# LAUNCHXL-F28379D_2.net
KiCad netlist of a schematic drawn in Altium Designer
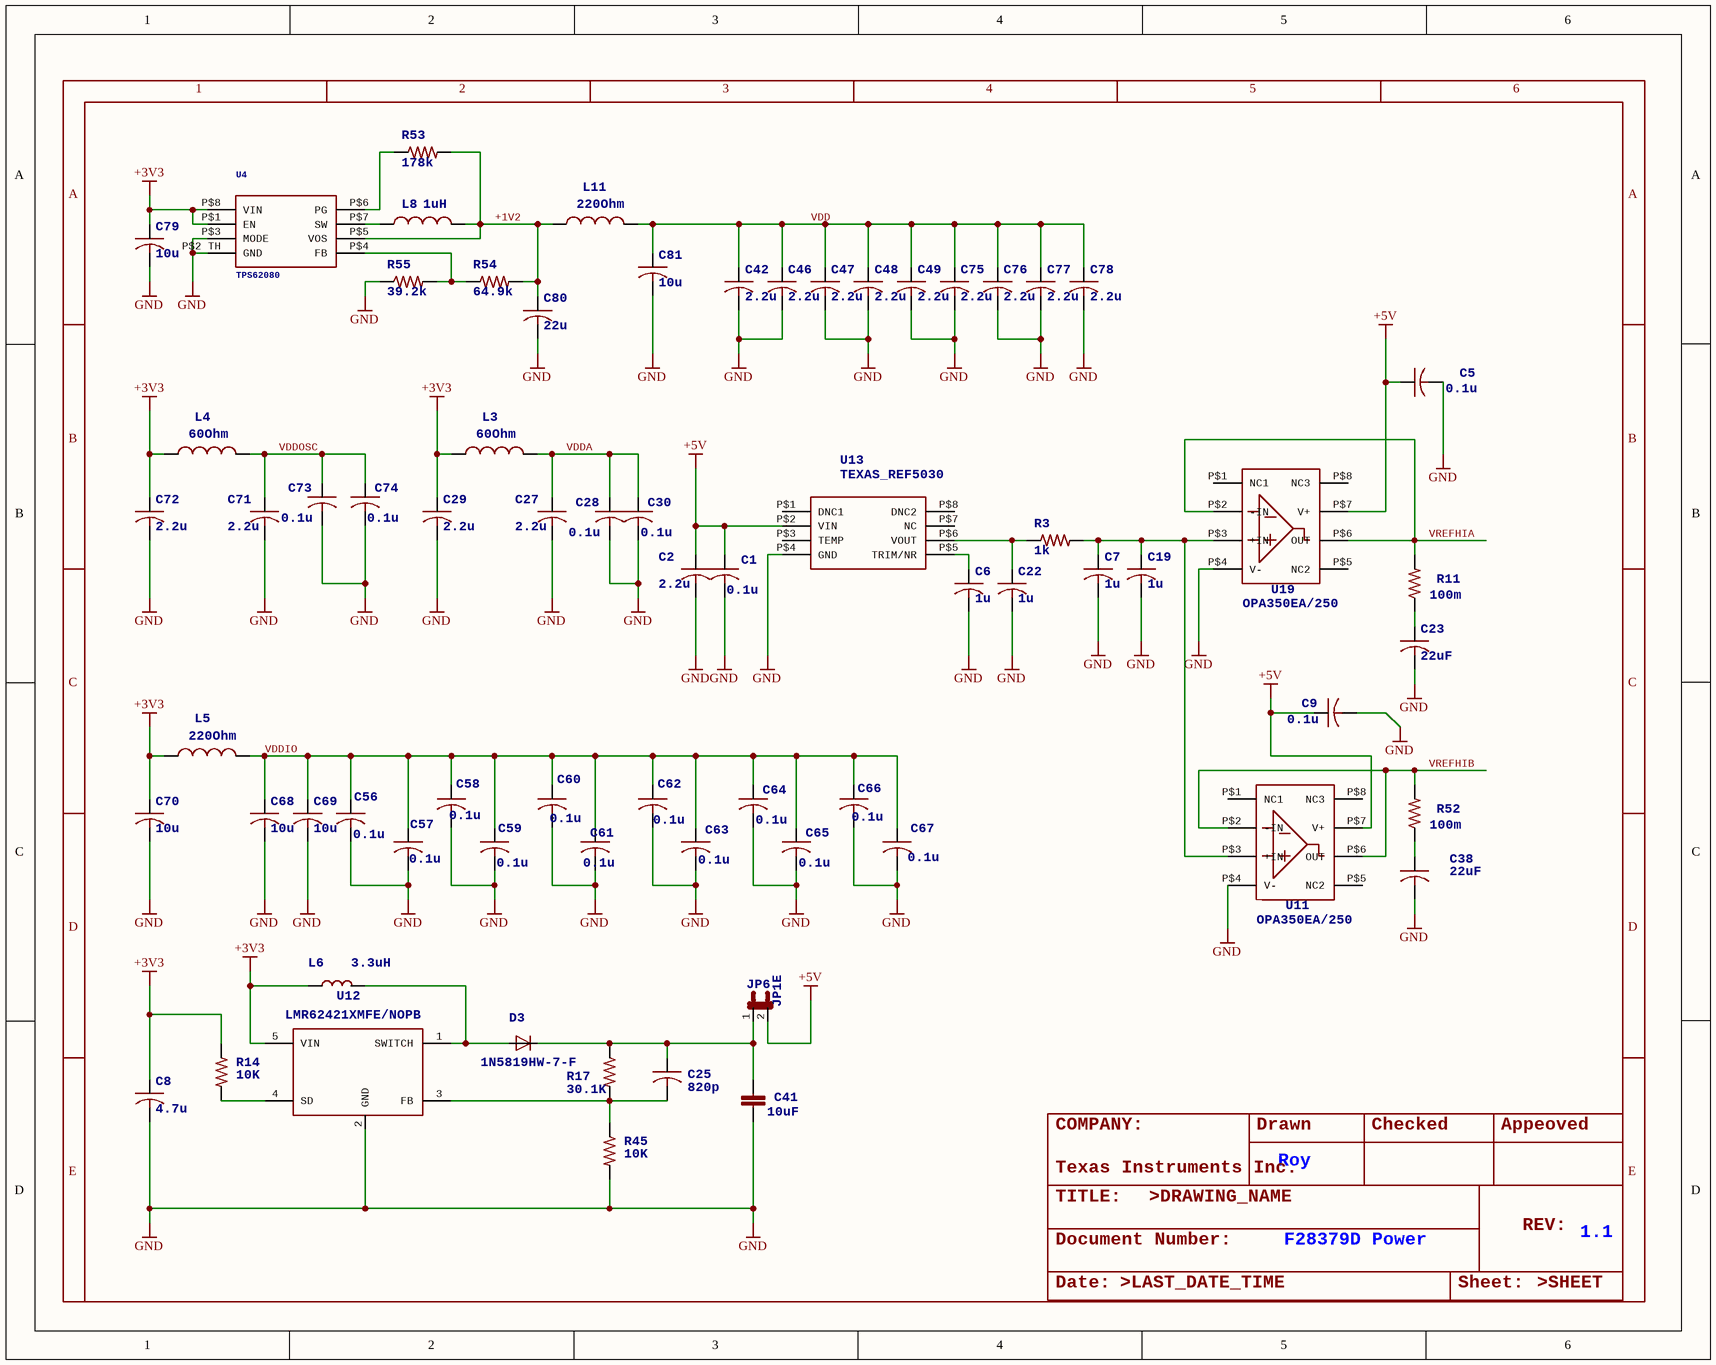
[diagram p0: LAUNCHXL-F28379D_2.SchDoc]

(export (version "E")
  (design (tool "Eeschema 10.0.6"))
  (components
    (comp (ref "C1")
      (value "0.1u")
      (footprint "C0402")
      (description "<B>CAPACITOR</B>, American symbol")
      (libsource (lib "rcl") (part "C-USC0402"))
    )
    (comp (ref "C2")
      (value "2.2u")
      (footprint "C0402")
      (description "<B>CAPACITOR</B>, American symbol")
      (libsource (lib "rcl") (part "C-USC0402"))
    )
    (comp (ref "C5")
      (value "0.1u")
      (footprint "C0402")
      (description "<B>CAPACITOR</B>, American symbol")
      (libsource (lib "rcl") (part "C-USC0402"))
    )
    (comp (ref "C6")
      (value "1u")
      (footprint "C0402")
      (description "<B>CAPACITOR</B>, American symbol")
      (libsource (lib "rcl") (part "C-USC0402"))
    )
    (comp (ref "C7")
      (value "1u")
      (footprint "C0402")
      (description "<B>CAPACITOR</B>, American symbol")
      (libsource (lib "rcl") (part "C-USC0402"))
    )
    (comp (ref "C8")
      (value "4.7u")
      (footprint "C0402")
      (description "<B>CAPACITOR</B>, American symbol")
      (libsource (lib "rcl") (part "C-USC0402"))
    )
    (comp (ref "C9")
      (value "0.1u")
      (footprint "C0402")
      (description "<B>CAPACITOR</B>, American symbol")
      (libsource (lib "rcl") (part "C-USC0402"))
    )
    (comp (ref "C19")
      (value "1u")
      (footprint "C0402")
      (description "<B>CAPACITOR</B>, American symbol")
      (libsource (lib "rcl") (part "C-USC0402"))
    )
    (comp (ref "C22")
      (value "1u")
      (footprint "C0402")
      (description "<B>CAPACITOR</B>, American symbol")
      (libsource (lib "rcl") (part "C-USC0402"))
    )
    (comp (ref "C23")
      (value "22uF")
      (footprint "C0603")
      (description "<B>CAPACITOR</B>, American symbol")
      (libsource (lib "rcl") (part "C-USC0603"))
    )
    (comp (ref "C25")
      (value "820p")
      (footprint "C0402")
      (description "<B>CAPACITOR</B>, American symbol")
      (libsource (lib "rcl") (part "C-USC0402"))
    )
    (comp (ref "C27")
      (value "2.2u")
      (footprint "C0402")
      (description "<B>CAPACITOR</B>, American symbol")
      (libsource (lib "rcl") (part "C-USC0402"))
    )
    (comp (ref "C28")
      (value "0.1u")
      (footprint "C0402")
      (description "<B>CAPACITOR</B>, American symbol")
      (libsource (lib "rcl") (part "C-USC0402"))
    )
    (comp (ref "C29")
      (value "2.2u")
      (footprint "C0402")
      (description "<B>CAPACITOR</B>, American symbol")
      (libsource (lib "rcl") (part "C-USC0402"))
    )
    (comp (ref "C30")
      (value "0.1u")
      (footprint "C0402")
      (description "<B>CAPACITOR</B>, American symbol")
      (libsource (lib "rcl") (part "C-USC0402"))
    )
    (comp (ref "C38")
      (value "22uF")
      (footprint "C0603")
      (description "<B>CAPACITOR</B>, American symbol")
      (libsource (lib "rcl") (part "C-USC0603"))
    )
    (comp (ref "C41")
      (value "10uF")
      (footprint "SPARKFUN_1210")
      (description "<b>Capacitor</b>\nStandard 0603 ceramic capacitor, and 0.1\" leaded capacitor.")
      (libsource (lib "RF430FRL152H_EVM_a") (part "SPARKFUN_CAP1210"))
    )
    (comp (ref "C42")
      (value "2.2u")
      (footprint "C0402")
      (description "<B>CAPACITOR</B>, American symbol")
      (libsource (lib "rcl") (part "C-USC0402"))
    )
    (comp (ref "C46")
      (value "2.2u")
      (footprint "C0402")
      (description "<B>CAPACITOR</B>, American symbol")
      (libsource (lib "rcl") (part "C-USC0402"))
    )
    (comp (ref "C47")
      (value "2.2u")
      (footprint "C0402")
      (description "<B>CAPACITOR</B>, American symbol")
      (libsource (lib "rcl") (part "C-USC0402"))
    )
    (comp (ref "C48")
      (value "2.2u")
      (footprint "C0402")
      (description "<B>CAPACITOR</B>, American symbol")
      (libsource (lib "rcl") (part "C-USC0402"))
    )
    (comp (ref "C49")
      (value "2.2u")
      (footprint "C0402")
      (description "<B>CAPACITOR</B>, American symbol")
      (libsource (lib "rcl") (part "C-USC0402"))
    )
    (comp (ref "C56")
      (value "0.1u")
      (footprint "C0402")
      (description "<B>CAPACITOR</B>, American symbol")
      (libsource (lib "rcl") (part "C-USC0402"))
    )
    (comp (ref "C57")
      (value "0.1u")
      (footprint "C0402")
      (description "<B>CAPACITOR</B>, American symbol")
      (libsource (lib "") (part "C-USC0402_1"))
    )
    (comp (ref "C58")
      (value "0.1u")
      (footprint "C0402")
      (description "<B>CAPACITOR</B>, American symbol")
      (libsource (lib "rcl") (part "C-USC0402"))
    )
    (comp (ref "C59")
      (value "0.1u")
      (footprint "C0402")
      (description "<B>CAPACITOR</B>, American symbol")
      (libsource (lib "rcl") (part "C-USC0402"))
    )
    (comp (ref "C60")
      (value "0.1u")
      (footprint "C0402")
      (description "<B>CAPACITOR</B>, American symbol")
      (libsource (lib "rcl") (part "C-USC0402"))
    )
    (comp (ref "C61")
      (value "0.1u")
      (footprint "C0402")
      (description "<B>CAPACITOR</B>, American symbol")
      (libsource (lib "rcl") (part "C-USC0402"))
    )
    (comp (ref "C62")
      (value "0.1u")
      (footprint "C0402")
      (description "<B>CAPACITOR</B>, American symbol")
      (libsource (lib "rcl") (part "C-USC0402"))
    )
    (comp (ref "C63")
      (value "0.1u")
      (footprint "C0402")
      (description "<B>CAPACITOR</B>, American symbol")
      (libsource (lib "rcl") (part "C-USC0402"))
    )
    (comp (ref "C64")
      (value "0.1u")
      (footprint "C0402")
      (description "<B>CAPACITOR</B>, American symbol")
      (libsource (lib "rcl") (part "C-USC0402"))
    )
    (comp (ref "C65")
      (value "0.1u")
      (footprint "C0402")
      (description "<B>CAPACITOR</B>, American symbol")
      (libsource (lib "rcl") (part "C-USC0402"))
    )
    (comp (ref "C66")
      (value "0.1u")
      (footprint "C0402")
      (description "<B>CAPACITOR</B>, American symbol")
      (libsource (lib "rcl") (part "C-USC0402"))
    )
    (comp (ref "C67")
      (value "0.1u")
      (footprint "C0402")
      (description "<B>CAPACITOR</B>, American symbol")
      (libsource (lib "rcl") (part "C-USC0402"))
    )
    (comp (ref "C68")
      (value "10u")
      (footprint "C0603")
      (description "<B>CAPACITOR</B>, American symbol")
      (libsource (lib "rcl") (part "C-USC0603"))
    )
    (comp (ref "C69")
      (value "10u")
      (footprint "C0603")
      (description "<B>CAPACITOR</B>, American symbol")
      (libsource (lib "rcl") (part "C-USC0603"))
    )
    (comp (ref "C70")
      (value "10u")
      (footprint "C0603")
      (description "<B>CAPACITOR</B>, American symbol")
      (libsource (lib "rcl") (part "C-USC0603"))
    )
    (comp (ref "C71")
      (value "2.2u")
      (footprint "C0402")
      (description "<B>CAPACITOR</B>, American symbol")
      (libsource (lib "rcl") (part "C-USC0402"))
    )
    (comp (ref "C72")
      (value "2.2u")
      (footprint "C0402")
      (description "<B>CAPACITOR</B>, American symbol")
      (libsource (lib "rcl") (part "C-USC0402"))
    )
    (comp (ref "C73")
      (value "0.1u")
      (footprint "C0402")
      (description "<B>CAPACITOR</B>, American symbol")
      (libsource (lib "rcl") (part "C-USC0402"))
    )
    (comp (ref "C74")
      (value "0.1u")
      (footprint "C0402")
      (description "<B>CAPACITOR</B>, American symbol")
      (libsource (lib "rcl") (part "C-USC0402"))
    )
    (comp (ref "C75")
      (value "2.2u")
      (footprint "C0402")
      (description "<B>CAPACITOR</B>, American symbol")
      (libsource (lib "rcl") (part "C-USC0402"))
    )
    (comp (ref "C76")
      (value "2.2u")
      (footprint "C0402")
      (description "<B>CAPACITOR</B>, American symbol")
      (libsource (lib "rcl") (part "C-USC0402"))
    )
    (comp (ref "C77")
      (value "2.2u")
      (footprint "C0402")
      (description "<B>CAPACITOR</B>, American symbol")
      (libsource (lib "rcl") (part "C-USC0402"))
    )
    (comp (ref "C78")
      (value "2.2u")
      (footprint "C0402")
      (description "<B>CAPACITOR</B>, American symbol")
      (libsource (lib "rcl") (part "C-USC0402"))
    )
    (comp (ref "C79")
      (value "10u")
      (footprint "C0603")
      (description "<B>CAPACITOR</B>, American symbol")
      (libsource (lib "rcl") (part "C-USC0603"))
    )
    (comp (ref "C80")
      (value "22u")
      (footprint "C0603")
      (description "<B>CAPACITOR</B>, American symbol")
      (libsource (lib "rcl") (part "C-USC0603"))
    )
    (comp (ref "C81")
      (value "10u")
      (footprint "C0603")
      (description "<B>CAPACITOR</B>, American symbol")
      (libsource (lib "rcl") (part "C-USC0603"))
    )
    (comp (ref "D3")
      (value "1N5819HW-7-F")
      (footprint "SOD123")
      (description "<B>DIODE</B><p>\nhigh speed (Philips)")
      (libsource (lib "diode") (part "1N4148"))
    )
    (comp (ref "JP6")
      (value "JP1E")
      (footprint "JP1")
      (description "<b>JUMPER</b>")
      (libsource (lib "jumper") (part "JP1E"))
    )
    (comp (ref "L3")
      (value "60Ohm")
      (footprint "R0402")
      (description "<B>INDUCTOR</B>, American symbol")
      (libsource (lib "rcl") (part "L-US0402"))
    )
    (comp (ref "L4")
      (value "60Ohm")
      (footprint "R0402")
      (description "<B>INDUCTOR</B>, American symbol")
      (libsource (lib "rcl") (part "L-US0402"))
    )
    (comp (ref "L5")
      (value "220Ohm")
      (footprint "R0402")
      (description "<B>INDUCTOR</B>, American symbol")
      (libsource (lib "rcl") (part "L-US0402"))
    )
    (comp (ref "L6")
      (value "3.3uH")
      (footprint "INDUCT-3_7*3_5")
      (libsource (lib "LAUNCHXL-F28027") (part "VLF4012A"))
    )
    (comp (ref "L8")
      (value "1uH")
      (footprint "L1212")
      (description "<B>INDUCTOR</B>, American symbol")
      (libsource (lib "LAUNCHXL-F28377S") (part "L-USL1212"))
    )
    (comp (ref "L11")
      (value "220Ohm")
      (footprint "R0402")
      (description "<B>INDUCTOR</B>, American symbol")
      (libsource (lib "rcl") (part "L-US0402"))
    )
    (comp (ref "R3")
      (value "1k")
      (footprint "R0402")
      (description "<B>RESISTOR</B>, American symbol")
      (libsource (lib "rcl") (part "R-US_R0402"))
    )
    (comp (ref "R11")
      (value "100m")
      (footprint "R0402")
      (description "<B>RESISTOR</B>, American symbol")
      (libsource (lib "rcl") (part "R-US_R0402"))
    )
    (comp (ref "R14")
      (value "10K")
      (footprint "R0402")
      (description "<B>RESISTOR</B>, American symbol")
      (libsource (lib "rcl") (part "R-US_R0402"))
    )
    (comp (ref "R17")
      (value "30.1K")
      (footprint "R0402")
      (description "<B>RESISTOR</B>, American symbol")
      (libsource (lib "rcl") (part "R-US_R0402"))
    )
    (comp (ref "R45")
      (value "10K")
      (footprint "R0402")
      (description "<B>RESISTOR</B>, American symbol")
      (libsource (lib "rcl") (part "R-US_R0402"))
    )
    (comp (ref "R52")
      (value "100m")
      (footprint "R0402")
      (description "<B>RESISTOR</B>, American symbol")
      (libsource (lib "rcl") (part "R-US_R0402"))
    )
    (comp (ref "R53")
      (value "178k")
      (footprint "R0402")
      (description "<B>RESISTOR</B>, American symbol")
      (libsource (lib "rcl") (part "R-US_R0402"))
    )
    (comp (ref "R54")
      (value "64.9k")
      (footprint "R0402")
      (description "<B>RESISTOR</B>, American symbol")
      (libsource (lib "rcl") (part "R-US_R0402"))
    )
    (comp (ref "R55")
      (value "39.2k")
      (footprint "R0402")
      (description "<B>RESISTOR</B>, American symbol")
      (libsource (lib "rcl") (part "R-US_R0402"))
    )
    (comp (ref "U4")
      (value "TPS62080")
      (footprint "SON8")
      (libsource (lib "LAUNCHXL-F28377S") (part "TPS62080"))
    )
    (comp (ref "U11")
      (value "OPA350EA/250")
      (footprint "OPA350_OPA350")
      (libsource (lib "OPA350") (part "OPA350_OPA350"))
    )
    (comp (ref "U12")
      (value "LMR62421XMFE/NOPB")
      (footprint "SOT23-5-DBV")
      (libsource (lib "LAUNCHXL-F28027") (part "LMR62421XMFE/NOPB"))
    )
    (comp (ref "U13")
      (value "TEXAS_REF5030")
      (footprint "TEXAS_REF5030")
      (libsource (lib "texas") (part "TEXAS_REF5030"))
    )
    (comp (ref "U19")
      (value "OPA350EA/250")
      (footprint "OPA350_OPA350")
      (libsource (lib "OPA350") (part "OPA350_OPA350"))
    )
  )
  (nets
    (net (code "1") (name "+3V3") (class "Default")
      (node (ref "C29") (pin "1") (pinfunction "1_1") (pintype "passive"))
      (node (ref "C70") (pin "1") (pinfunction "1_1") (pintype "passive"))
      (node (ref "C72") (pin "1") (pinfunction "1_1") (pintype "passive"))
      (node (ref "C79") (pin "1") (pinfunction "1_1") (pintype "passive"))
      (node (ref "C8") (pin "1") (pinfunction "1_1") (pintype "passive"))
      (node (ref "L3") (pin "1") (pinfunction "1_1") (pintype "passive"))
      (node (ref "L4") (pin "1") (pinfunction "1_1") (pintype "passive"))
      (node (ref "L5") (pin "1") (pinfunction "1_1") (pintype "passive"))
      (node (ref "L6") (pin "P$1") (pinfunction "1_P$1") (pintype "passive"))
      (node (ref "R14") (pin "1") (pinfunction "1_1") (pintype "passive"))
      (node (ref "U12") (pin "5") (pinfunction "VIN_5") (pintype "passive"))
      (node (ref "U4") (pin "P$1") (pinfunction "EN_P$1") (pintype "passive"))
      (node (ref "U4") (pin "P$8") (pinfunction "VIN_P$8") (pintype "passive"))
    )
    (net (code "2") (name "+5V") (class "Default")
      (node (ref "C1") (pin "1") (pinfunction "1_1") (pintype "passive"))
      (node (ref "C2") (pin "1") (pinfunction "1_1") (pintype "passive"))
      (node (ref "C5") (pin "1") (pinfunction "1_1") (pintype "passive"))
      (node (ref "C9") (pin "1") (pinfunction "1_1") (pintype "passive"))
      (node (ref "JP6") (pin "2") (pinfunction "2_2") (pintype "passive"))
      (node (ref "U11") (pin "P$7") (pinfunction "V+_P$7") (pintype "passive"))
      (node (ref "U13") (pin "P$2") (pinfunction "VIN_P$2") (pintype "passive"))
      (node (ref "U19") (pin "P$7") (pinfunction "V+_P$7") (pintype "passive"))
    )
    (net (code "3") (name "/+1V2") (class "Default")
      (node (ref "C80") (pin "1") (pinfunction "1_1") (pintype "passive"))
      (node (ref "L11") (pin "1") (pinfunction "1_1") (pintype "passive"))
      (node (ref "L8") (pin "P$2") (pinfunction "2_P$2") (pintype "passive"))
      (node (ref "R53") (pin "2") (pinfunction "2_2") (pintype "passive"))
      (node (ref "R54") (pin "2") (pinfunction "2_2") (pintype "passive"))
      (node (ref "U4") (pin "P$5") (pinfunction "VOS_P$5") (pintype "passive"))
    )
    (net (code "4") (name "/VDD") (class "Default")
      (node (ref "C42") (pin "1") (pinfunction "1_1") (pintype "passive"))
      (node (ref "C46") (pin "1") (pinfunction "1_1") (pintype "passive"))
      (node (ref "C47") (pin "1") (pinfunction "1_1") (pintype "passive"))
      (node (ref "C48") (pin "1") (pinfunction "1_1") (pintype "passive"))
      (node (ref "C49") (pin "1") (pinfunction "1_1") (pintype "passive"))
      (node (ref "C75") (pin "1") (pinfunction "1_1") (pintype "passive"))
      (node (ref "C76") (pin "1") (pinfunction "1_1") (pintype "passive"))
      (node (ref "C77") (pin "1") (pinfunction "1_1") (pintype "passive"))
      (node (ref "C78") (pin "1") (pinfunction "1_1") (pintype "passive"))
      (node (ref "C81") (pin "1") (pinfunction "1_1") (pintype "passive"))
      (node (ref "L11") (pin "2") (pinfunction "2_2") (pintype "passive"))
    )
    (net (code "5") (name "/VDDA") (class "Default")
      (node (ref "C27") (pin "1") (pinfunction "1_1") (pintype "passive"))
      (node (ref "C28") (pin "1") (pinfunction "1_1") (pintype "passive"))
      (node (ref "C30") (pin "1") (pinfunction "1_1") (pintype "passive"))
      (node (ref "L3") (pin "2") (pinfunction "2_2") (pintype "passive"))
    )
    (net (code "6") (name "/VDDIO") (class "Default")
      (node (ref "C56") (pin "1") (pinfunction "1_1") (pintype "passive"))
      (node (ref "C57") (pin "1") (pinfunction "1_1") (pintype "passive"))
      (node (ref "C58") (pin "1") (pinfunction "1_1") (pintype "passive"))
      (node (ref "C59") (pin "1") (pinfunction "1_1") (pintype "passive"))
      (node (ref "C60") (pin "1") (pinfunction "1_1") (pintype "passive"))
      (node (ref "C61") (pin "1") (pinfunction "1_1") (pintype "passive"))
      (node (ref "C62") (pin "1") (pinfunction "1_1") (pintype "passive"))
      (node (ref "C63") (pin "1") (pinfunction "1_1") (pintype "passive"))
      (node (ref "C64") (pin "1") (pinfunction "1_1") (pintype "passive"))
      (node (ref "C65") (pin "1") (pinfunction "1_1") (pintype "passive"))
      (node (ref "C66") (pin "1") (pinfunction "1_1") (pintype "passive"))
      (node (ref "C67") (pin "1") (pinfunction "1_1") (pintype "passive"))
      (node (ref "C68") (pin "1") (pinfunction "1_1") (pintype "passive"))
      (node (ref "C69") (pin "1") (pinfunction "1_1") (pintype "passive"))
      (node (ref "L5") (pin "2") (pinfunction "2_2") (pintype "passive"))
    )
    (net (code "7") (name "/VDDOSC") (class "Default")
      (node (ref "C71") (pin "1") (pinfunction "1_1") (pintype "passive"))
      (node (ref "C73") (pin "1") (pinfunction "1_1") (pintype "passive"))
      (node (ref "C74") (pin "1") (pinfunction "1_1") (pintype "passive"))
      (node (ref "L4") (pin "2") (pinfunction "2_2") (pintype "passive"))
    )
    (net (code "8") (name "/VREFHIA") (class "Default")
      (node (ref "R11") (pin "2") (pinfunction "2_2") (pintype "passive"))
      (node (ref "U19") (pin "P$2") (pinfunction "-IN_P$2") (pintype "passive"))
      (node (ref "U19") (pin "P$6") (pinfunction "OUT_P$6") (pintype "passive"))
    )
    (net (code "9") (name "/VREFHIB") (class "Default")
      (node (ref "R52") (pin "2") (pinfunction "2_2") (pintype "passive"))
      (node (ref "U11") (pin "P$2") (pinfunction "-IN_P$2") (pintype "passive"))
      (node (ref "U11") (pin "P$6") (pinfunction "OUT_P$6") (pintype "passive"))
    )
    (net (code "10") (name "GND") (class "Default")
      (node (ref "C1") (pin "2") (pinfunction "2_2") (pintype "passive"))
      (node (ref "C19") (pin "2") (pinfunction "2_2") (pintype "passive"))
      (node (ref "C2") (pin "2") (pinfunction "2_2") (pintype "passive"))
      (node (ref "C22") (pin "2") (pinfunction "2_2") (pintype "passive"))
      (node (ref "C23") (pin "2") (pinfunction "2_2") (pintype "passive"))
      (node (ref "C27") (pin "2") (pinfunction "2_2") (pintype "passive"))
      (node (ref "C28") (pin "2") (pinfunction "2_2") (pintype "passive"))
      (node (ref "C29") (pin "2") (pinfunction "2_2") (pintype "passive"))
      (node (ref "C30") (pin "2") (pinfunction "2_2") (pintype "passive"))
      (node (ref "C38") (pin "2") (pinfunction "2_2") (pintype "passive"))
      (node (ref "C41") (pin "1") (pinfunction "1_1") (pintype "passive"))
      (node (ref "C42") (pin "2") (pinfunction "2_2") (pintype "passive"))
      (node (ref "C46") (pin "2") (pinfunction "2_2") (pintype "passive"))
      (node (ref "C47") (pin "2") (pinfunction "2_2") (pintype "passive"))
      (node (ref "C48") (pin "2") (pinfunction "2_2") (pintype "passive"))
      (node (ref "C49") (pin "2") (pinfunction "2_2") (pintype "passive"))
      (node (ref "C5") (pin "2") (pinfunction "2_2") (pintype "passive"))
      (node (ref "C56") (pin "2") (pinfunction "2_2") (pintype "passive"))
      (node (ref "C57") (pin "2") (pinfunction "2_2") (pintype "passive"))
      (node (ref "C58") (pin "2") (pinfunction "2_2") (pintype "passive"))
      (node (ref "C59") (pin "2") (pinfunction "2_2") (pintype "passive"))
      (node (ref "C6") (pin "2") (pinfunction "2_2") (pintype "passive"))
      (node (ref "C60") (pin "2") (pinfunction "2_2") (pintype "passive"))
      (node (ref "C61") (pin "2") (pinfunction "2_2") (pintype "passive"))
      (node (ref "C62") (pin "2") (pinfunction "2_2") (pintype "passive"))
      (node (ref "C63") (pin "2") (pinfunction "2_2") (pintype "passive"))
      (node (ref "C64") (pin "2") (pinfunction "2_2") (pintype "passive"))
      (node (ref "C65") (pin "2") (pinfunction "2_2") (pintype "passive"))
      (node (ref "C66") (pin "2") (pinfunction "2_2") (pintype "passive"))
      (node (ref "C67") (pin "2") (pinfunction "2_2") (pintype "passive"))
      (node (ref "C68") (pin "2") (pinfunction "2_2") (pintype "passive"))
      (node (ref "C69") (pin "2") (pinfunction "2_2") (pintype "passive"))
      (node (ref "C7") (pin "2") (pinfunction "2_2") (pintype "passive"))
      (node (ref "C70") (pin "2") (pinfunction "2_2") (pintype "passive"))
      (node (ref "C71") (pin "2") (pinfunction "2_2") (pintype "passive"))
      (node (ref "C72") (pin "2") (pinfunction "2_2") (pintype "passive"))
      (node (ref "C73") (pin "2") (pinfunction "2_2") (pintype "passive"))
      (node (ref "C74") (pin "2") (pinfunction "2_2") (pintype "passive"))
      (node (ref "C75") (pin "2") (pinfunction "2_2") (pintype "passive"))
      (node (ref "C76") (pin "2") (pinfunction "2_2") (pintype "passive"))
      (node (ref "C77") (pin "2") (pinfunction "2_2") (pintype "passive"))
      (node (ref "C78") (pin "2") (pinfunction "2_2") (pintype "passive"))
      (node (ref "C79") (pin "2") (pinfunction "2_2") (pintype "passive"))
      (node (ref "C8") (pin "2") (pinfunction "2_2") (pintype "passive"))
      (node (ref "C80") (pin "2") (pinfunction "2_2") (pintype "passive"))
      (node (ref "C81") (pin "2") (pinfunction "2_2") (pintype "passive"))
      (node (ref "C9") (pin "2") (pinfunction "2_2") (pintype "passive"))
      (node (ref "R45") (pin "2") (pinfunction "2_2") (pintype "passive"))
      (node (ref "R55") (pin "1") (pinfunction "1_1") (pintype "passive"))
      (node (ref "U11") (pin "P$4") (pinfunction "V-_P$4") (pintype "passive"))
      (node (ref "U12") (pin "2") (pinfunction "GND_2") (pintype "passive"))
      (node (ref "U13") (pin "P$4") (pinfunction "GND_P$4") (pintype "passive"))
      (node (ref "U19") (pin "P$4") (pinfunction "V-_P$4") (pintype "passive"))
      (node (ref "U4") (pin "P$2_TH") (pinfunction "GND_P$2_TH") (pintype "passive"))
      (node (ref "U4") (pin "P$3") (pinfunction "MODE_P$3") (pintype "passive"))
    )
    (net (code "11") (name "Net-(C23-Pad1)") (class "Default")
      (node (ref "C23") (pin "1") (pinfunction "1_1") (pintype "passive"))
      (node (ref "R11") (pin "1") (pinfunction "1_1") (pintype "passive"))
    )
    (net (code "12") (name "Net-(C25-Pad1)") (class "Default")
      (node (ref "C25") (pin "1") (pinfunction "1_1") (pintype "passive"))
      (node (ref "C41") (pin "2") (pinfunction "2_2") (pintype "passive"))
      (node (ref "D3") (pin "C") (pinfunction "C_C") (pintype "passive"))
      (node (ref "JP6") (pin "1") (pinfunction "1_1") (pintype "passive"))
      (node (ref "R17") (pin "1") (pinfunction "1_1") (pintype "passive"))
    )
    (net (code "13") (name "Net-(C38-Pad1)") (class "Default")
      (node (ref "C38") (pin "1") (pinfunction "1_1") (pintype "passive"))
      (node (ref "R52") (pin "1") (pinfunction "1_1") (pintype "passive"))
    )
    (net (code "14") (name "Net-(L6-2)") (class "Default")
      (node (ref "D3") (pin "A") (pinfunction "A_A") (pintype "passive"))
      (node (ref "L6") (pin "P$2") (pinfunction "2_P$2") (pintype "passive"))
      (node (ref "U12") (pin "1") (pinfunction "SWITCH_1") (pintype "passive"))
    )
    (net (code "15") (name "Net-(L8-1)") (class "Default")
      (node (ref "L8") (pin "P$1") (pinfunction "1_P$1") (pintype "passive"))
      (node (ref "U4") (pin "P$7") (pinfunction "SW_P$7") (pintype "passive"))
    )
    (net (code "16") (name "Net-(U4-FB)") (class "Default")
      (node (ref "R54") (pin "1") (pinfunction "1_1") (pintype "passive"))
      (node (ref "R55") (pin "2") (pinfunction "2_2") (pintype "passive"))
      (node (ref "U4") (pin "P$4") (pinfunction "FB_P$4") (pintype "passive"))
    )
    (net (code "17") (name "Net-(U4-PG)") (class "Default")
      (node (ref "R53") (pin "1") (pinfunction "1_1") (pintype "passive"))
      (node (ref "U4") (pin "P$6") (pinfunction "PG_P$6") (pintype "passive"))
    )
    (net (code "18") (name "Net-(U11-+IN)") (class "Default")
      (node (ref "C19") (pin "1") (pinfunction "1_1") (pintype "passive"))
      (node (ref "C7") (pin "1") (pinfunction "1_1") (pintype "passive"))
      (node (ref "R3") (pin "2") (pinfunction "2_2") (pintype "passive"))
      (node (ref "U11") (pin "P$3") (pinfunction "+IN_P$3") (pintype "passive"))
      (node (ref "U19") (pin "P$3") (pinfunction "+IN_P$3") (pintype "passive"))
    )
    (net (code "19") (name "Net-(U12-FB)") (class "Default")
      (node (ref "C25") (pin "2") (pinfunction "2_2") (pintype "passive"))
      (node (ref "R17") (pin "2") (pinfunction "2_2") (pintype "passive"))
      (node (ref "R45") (pin "1") (pinfunction "1_1") (pintype "passive"))
      (node (ref "U12") (pin "3") (pinfunction "FB_3") (pintype "passive"))
    )
    (net (code "20") (name "Net-(U12-SD)") (class "Default")
      (node (ref "R14") (pin "2") (pinfunction "2_2") (pintype "passive"))
      (node (ref "U12") (pin "4") (pinfunction "SD_4") (pintype "passive"))
    )
    (net (code "21") (name "Net-(U13-TRIM{slash}NR)") (class "Default")
      (node (ref "C6") (pin "1") (pinfunction "1_1") (pintype "passive"))
      (node (ref "U13") (pin "P$5") (pinfunction "TRIM/NR_P$5") (pintype "passive"))
    )
    (net (code "22") (name "Net-(U13-VOUT)") (class "Default")
      (node (ref "C22") (pin "1") (pinfunction "1_1") (pintype "passive"))
      (node (ref "R3") (pin "1") (pinfunction "1_1") (pintype "passive"))
      (node (ref "U13") (pin "P$6") (pinfunction "VOUT_P$6") (pintype "passive"))
    )
    (net (code "23") (name "unconnected-(U11-NC1-PadP$1)") (class "Default")
      (node (ref "U11") (pin "P$1") (pinfunction "NC1_P$1") (pintype "passive"))
    )
    (net (code "24") (name "unconnected-(U11-NC2-PadP$5)") (class "Default")
      (node (ref "U11") (pin "P$5") (pinfunction "NC2_P$5") (pintype "passive"))
    )
    (net (code "25") (name "unconnected-(U11-NC3-PadP$8)") (class "Default")
      (node (ref "U11") (pin "P$8") (pinfunction "NC3_P$8") (pintype "passive"))
    )
    (net (code "26") (name "unconnected-(U13-DNC1-PadP$1)") (class "Default")
      (node (ref "U13") (pin "P$1") (pinfunction "DNC1_P$1") (pintype "passive"))
    )
    (net (code "27") (name "unconnected-(U13-DNC2-PadP$8)") (class "Default")
      (node (ref "U13") (pin "P$8") (pinfunction "DNC2_P$8") (pintype "passive"))
    )
    (net (code "28") (name "unconnected-(U13-NC-PadP$7)") (class "Default")
      (node (ref "U13") (pin "P$7") (pinfunction "NC_P$7") (pintype "passive"))
    )
    (net (code "29") (name "unconnected-(U13-TEMP-PadP$3)") (class "Default")
      (node (ref "U13") (pin "P$3") (pinfunction "TEMP_P$3") (pintype "passive"))
    )
    (net (code "30") (name "unconnected-(U19-NC1-PadP$1)") (class "Default")
      (node (ref "U19") (pin "P$1") (pinfunction "NC1_P$1") (pintype "passive"))
    )
    (net (code "31") (name "unconnected-(U19-NC2-PadP$5)") (class "Default")
      (node (ref "U19") (pin "P$5") (pinfunction "NC2_P$5") (pintype "passive"))
    )
    (net (code "32") (name "unconnected-(U19-NC3-PadP$8)") (class "Default")
      (node (ref "U19") (pin "P$8") (pinfunction "NC3_P$8") (pintype "passive"))
    )
  )
)
